# PD_Filter_Amp.net
KiCad netlist of a schematic drawn in EAGLE
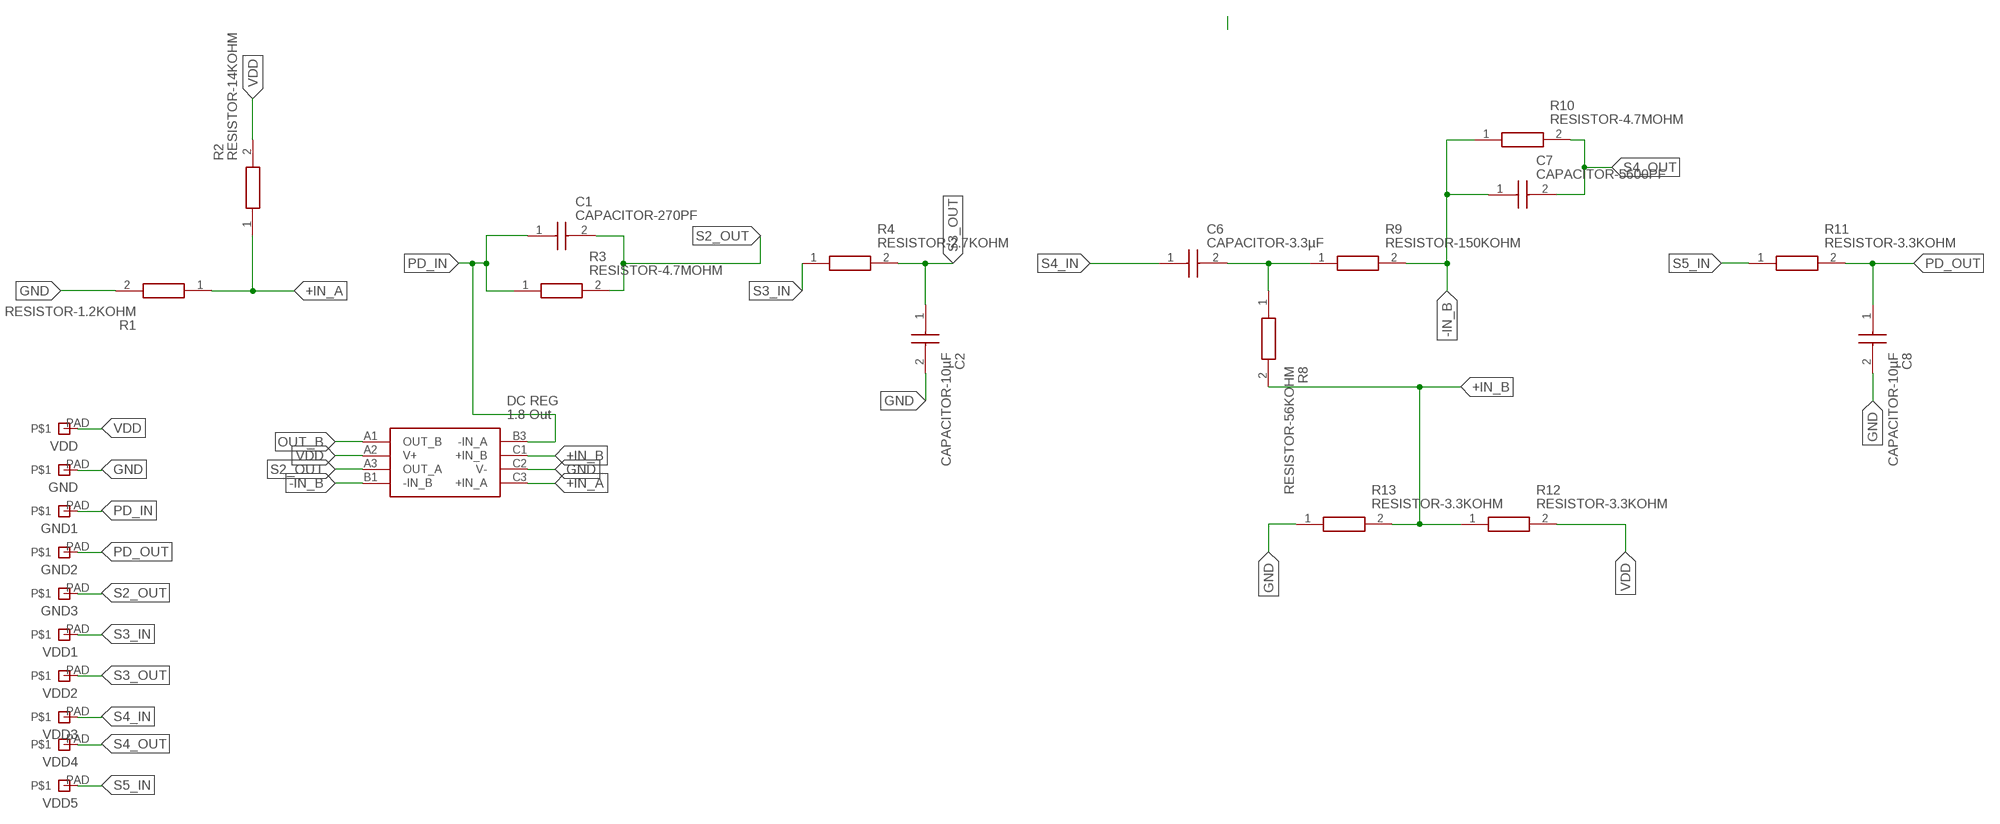
[diagram p0: schematic, sheet 1]

(export (version "E")
  (design (tool "Eeschema 10.0.6"))
  (components
    (comp (ref "C1")
      (value "CAPACITOR-270PF")
      (footprint "eagle-import:CAPC1005X55N")
      (fields
        (field (name "MANUFACTURER_PART_NUMBER") "C0402C271G5GACTU")
        (field (name "MOUSER_PART_NUMBER") "80-C0402C271G5G")
      )
      (libsource (lib "eagle-import") (part "CAPACITOR-270PF"))
    )
    (comp (ref "C2")
      (value "CAPACITOR-10µF")
      (footprint "eagle-import:C0402")
      (fields
        (field (name "MANUFACTURER_PART_NUMBER") "C0402C106M9PACTU")
        (field (name "MOUSER_PART_NUMBER") "80-C0402C106M9P")
      )
      (libsource (lib "eagle-import") (part "CAPACITOR-10µF"))
    )
    (comp (ref "C6")
      (value "CAPACITOR-3.3µF")
      (footprint "eagle-import:C0402")
      (fields
        (field (name "MANUFACTURER_PART_NUMBER") "C0402C335M7PACTU")
        (field (name "MOUSER_PART_NUMBER") "80-C0402C335M7P")
      )
      (libsource (lib "eagle-import") (part "CAPACITOR-3.3µF"))
    )
    (comp (ref "C7")
      (value "CAPACITOR-5600PF")
      (footprint "eagle-import:CAPC1005X55N")
      (fields
        (field (name "MANUFACTURER_PART_NUMBER") "C0402C562J4RACTU")
        (field (name "MOUSER_PART_NUMBER") "80-C0402C562J4R")
      )
      (libsource (lib "eagle-import") (part "CAPACITOR-5600PF"))
    )
    (comp (ref "C8")
      (value "CAPACITOR-10µF")
      (footprint "eagle-import:C0402")
      (fields
        (field (name "MANUFACTURER_PART_NUMBER") "C0402C106M9PACTU")
        (field (name "MOUSER_PART_NUMBER") "80-C0402C106M9P")
      )
      (libsource (lib "eagle-import") (part "CAPACITOR-10µF"))
    )
    (comp (ref "GND")
      (value "PAD")
      (footprint "eagle-import:PAD")
      (libsource (lib "eagle-import") (part "PAD"))
    )
    (comp (ref "GND1")
      (value "PAD")
      (footprint "eagle-import:PAD")
      (libsource (lib "eagle-import") (part "PAD"))
    )
    (comp (ref "GND2")
      (value "PAD")
      (footprint "eagle-import:PAD")
      (libsource (lib "eagle-import") (part "PAD"))
    )
    (comp (ref "GND3")
      (value "PAD")
      (footprint "eagle-import:PAD")
      (libsource (lib "eagle-import") (part "PAD"))
    )
    (comp (ref "IC1")
      (value "ADA4505-2")
      (footprint "eagle-import:BGA8C50P3X3_142X142X65")
      (fields
        (field (name "MANUFACTURER_PART_NUMBER") "ADA4505-2ACBZ-R7")
        (field (name "MOUSER_PART_NUMBER") "584-ADA4505-2ACBZ-R7")
      )
      (libsource (lib "eagle-import") (part "ADA4505-2"))
    )
    (comp (ref "R1")
      (value "RESISTOR-1.2KOHM")
      (footprint "eagle-import:ERJPA2_(0402)")
      (fields
        (field (name "MANUFACTURER_PART_NUMBER") "ERJ-PA2D1201X")
        (field (name "MOUSER_PART_NUMBER") "667-ERJ-PA2D1201X")
      )
      (libsource (lib "eagle-import") (part "RESISTOR-1.2KOHM"))
    )
    (comp (ref "R2")
      (value "RESISTOR-14KOHM")
      (footprint "eagle-import:ERJ2RKD1004X")
      (fields
        (field (name "MANUFACTURER_PART_NUMBER") "ERJ-2RKF1402X")
        (field (name "MOUSER_PART_NUMBER") "667-ERJ-2RKF1402X")
      )
      (libsource (lib "eagle-import") (part "RESISTOR-14KOHM"))
    )
    (comp (ref "R3")
      (value "RESISTOR-4.7MOHM")
      (footprint "eagle-import:ERJ2RKD1004X")
      (fields
        (field (name "MANUFACTURER_PART_NUMBER") "ERJ-2GEJ475X")
        (field (name "MOUSER_PART_NUMBER") "667-ERJ-2GEJ475X")
      )
      (libsource (lib "eagle-import") (part "RESISTOR-4.7MOHM"))
    )
    (comp (ref "R4")
      (value "RESISTOR-2.7KOHM")
      (footprint "eagle-import:ERJPA2_(0402)")
      (fields (field (name "MANUFACTURER_PART_NUMBER") "ERJ-PA2F2701X"))
      (libsource (lib "eagle-import") (part "RESISTOR-2.7KOHM"))
    )
    (comp (ref "R8")
      (value "RESISTOR-56KOHM")
      (footprint "eagle-import:ERJ2RKD1004X")
      (fields
        (field (name "MANUFACTURER_PART_NUMBER") "ERJ-2RKF5602X")
        (field (name "MOUSER_PART_NUMBER") "667-ERJ-2RKF5602X")
      )
      (libsource (lib "eagle-import") (part "RESISTOR-56KOHM"))
    )
    (comp (ref "R9")
      (value "RESISTOR-150KOHM")
      (footprint "eagle-import:ERJS02_U02_(0402)")
      (fields
        (field (name "MANUFACTURER_PART_NUMBER") "ERJ-U02D1503X")
        (field (name "MOUSER_PART_NUMBER") "667-ERJ-U02D1503X")
      )
      (libsource (lib "eagle-import") (part "RESISTOR-150KOHM"))
    )
    (comp (ref "R10")
      (value "RESISTOR-4.7MOHM")
      (footprint "eagle-import:ERJ2RKD1004X")
      (fields
        (field (name "MANUFACTURER_PART_NUMBER") "ERJ-2GEJ475X")
        (field (name "MOUSER_PART_NUMBER") "667-ERJ-2GEJ475X")
      )
      (libsource (lib "eagle-import") (part "RESISTOR-4.7MOHM"))
    )
    (comp (ref "R11")
      (value "RESISTOR-3.3KOHM")
      (footprint "eagle-import:ERJPA2_(0402)")
      (fields
        (field (name "MANUFACTURER_PART_NUMBER") "ERJ-PA2F3301X")
        (field (name "MOUSER_PART_NUMBER") "667-ERJ-PA2F3301X")
      )
      (libsource (lib "eagle-import") (part "RESISTOR-3.3KOHM"))
    )
    (comp (ref "R12")
      (value "RESISTOR-3.3KOHM")
      (footprint "eagle-import:ERJPA2_(0402)")
      (fields
        (field (name "MANUFACTURER_PART_NUMBER") "ERJ-PA2F3301X")
        (field (name "MOUSER_PART_NUMBER") "667-ERJ-PA2F3301X")
      )
      (libsource (lib "eagle-import") (part "RESISTOR-3.3KOHM"))
    )
    (comp (ref "R13")
      (value "RESISTOR-3.3KOHM")
      (footprint "eagle-import:ERJPA2_(0402)")
      (fields
        (field (name "MANUFACTURER_PART_NUMBER") "ERJ-PA2F3301X")
        (field (name "MOUSER_PART_NUMBER") "667-ERJ-PA2F3301X")
      )
      (libsource (lib "eagle-import") (part "RESISTOR-3.3KOHM"))
    )
    (comp (ref "VDD")
      (value "PAD")
      (footprint "eagle-import:PAD")
      (libsource (lib "eagle-import") (part "PAD"))
    )
    (comp (ref "VDD1")
      (value "PAD")
      (footprint "eagle-import:PAD")
      (libsource (lib "eagle-import") (part "PAD"))
    )
    (comp (ref "VDD2")
      (value "PAD")
      (footprint "eagle-import:PAD")
      (libsource (lib "eagle-import") (part "PAD"))
    )
    (comp (ref "VDD3")
      (value "PAD")
      (footprint "eagle-import:PAD")
      (libsource (lib "eagle-import") (part "PAD"))
    )
    (comp (ref "VDD4")
      (value "PAD")
      (footprint "eagle-import:PAD")
      (libsource (lib "eagle-import") (part "PAD"))
    )
    (comp (ref "VDD5")
      (value "PAD")
      (footprint "eagle-import:PAD")
      (libsource (lib "eagle-import") (part "PAD"))
    )
  )
  (nets
    (net (code "1") (name "+IN_A") (class "Default")
      (node (ref "IC1") (pin "C3") (pinfunction "+IN_A_C3") (pintype "bidirectional"))
      (node (ref "R1") (pin "1") (pinfunction "1_1") (pintype "bidirectional"))
      (node (ref "R2") (pin "1") (pinfunction "1_1") (pintype "bidirectional"))
    )
    (net (code "2") (name "+IN_B") (class "Default")
      (node (ref "IC1") (pin "C1") (pinfunction "+IN_B_C1") (pintype "bidirectional"))
      (node (ref "R12") (pin "1") (pinfunction "1_1") (pintype "bidirectional"))
      (node (ref "R13") (pin "2") (pinfunction "2_2") (pintype "bidirectional"))
      (node (ref "R8") (pin "2") (pinfunction "2_2") (pintype "bidirectional"))
    )
    (net (code "3") (name "-IN_B") (class "Default")
      (node (ref "C7") (pin "1") (pinfunction "1_1") (pintype "bidirectional"))
      (node (ref "IC1") (pin "B1") (pinfunction "-IN_B_B1") (pintype "bidirectional"))
      (node (ref "R10") (pin "1") (pinfunction "1_1") (pintype "bidirectional"))
      (node (ref "R9") (pin "2") (pinfunction "2_2") (pintype "bidirectional"))
    )
    (net (code "4") (name "GND") (class "Default")
      (node (ref "C2") (pin "2") (pinfunction "2_2") (pintype "bidirectional"))
      (node (ref "C8") (pin "2") (pinfunction "2_2") (pintype "bidirectional"))
      (node (ref "GND") (pin "PAD") (pinfunction "P$1_PAD") (pintype "bidirectional"))
      (node (ref "IC1") (pin "C2") (pinfunction "V-_C2") (pintype "bidirectional"))
      (node (ref "R1") (pin "2") (pinfunction "2_2") (pintype "bidirectional"))
      (node (ref "R13") (pin "1") (pinfunction "1_1") (pintype "bidirectional"))
    )
    (net (code "5") (name "Net-(C6-Pad2)") (class "Default")
      (node (ref "C6") (pin "2") (pinfunction "2_2") (pintype "bidirectional"))
      (node (ref "R8") (pin "1") (pinfunction "1_1") (pintype "bidirectional"))
      (node (ref "R9") (pin "1") (pinfunction "1_1") (pintype "bidirectional"))
    )
    (net (code "6") (name "OUT_B") (class "Default")
      (node (ref "IC1") (pin "A1") (pinfunction "OUT_B_A1") (pintype "bidirectional"))
    )
    (net (code "7") (name "PD_IN") (class "Default")
      (node (ref "C1") (pin "1") (pinfunction "1_1") (pintype "bidirectional"))
      (node (ref "GND1") (pin "PAD") (pinfunction "P$1_PAD") (pintype "bidirectional"))
      (node (ref "IC1") (pin "B3") (pinfunction "-IN_A_B3") (pintype "bidirectional"))
      (node (ref "R3") (pin "1") (pinfunction "1_1") (pintype "bidirectional"))
    )
    (net (code "8") (name "PD_OUT") (class "Default")
      (node (ref "C8") (pin "1") (pinfunction "1_1") (pintype "bidirectional"))
      (node (ref "GND2") (pin "PAD") (pinfunction "P$1_PAD") (pintype "bidirectional"))
      (node (ref "R11") (pin "2") (pinfunction "2_2") (pintype "bidirectional"))
    )
    (net (code "9") (name "S2_OUT") (class "Default")
      (node (ref "C1") (pin "2") (pinfunction "2_2") (pintype "bidirectional"))
      (node (ref "GND3") (pin "PAD") (pinfunction "P$1_PAD") (pintype "bidirectional"))
      (node (ref "IC1") (pin "A3") (pinfunction "OUT_A_A3") (pintype "bidirectional"))
      (node (ref "R3") (pin "2") (pinfunction "2_2") (pintype "bidirectional"))
    )
    (net (code "10") (name "S3_IN") (class "Default")
      (node (ref "R4") (pin "1") (pinfunction "1_1") (pintype "bidirectional"))
      (node (ref "VDD1") (pin "PAD") (pinfunction "P$1_PAD") (pintype "bidirectional"))
    )
    (net (code "11") (name "S3_OUT") (class "Default")
      (node (ref "C2") (pin "1") (pinfunction "1_1") (pintype "bidirectional"))
      (node (ref "R4") (pin "2") (pinfunction "2_2") (pintype "bidirectional"))
      (node (ref "VDD2") (pin "PAD") (pinfunction "P$1_PAD") (pintype "bidirectional"))
    )
    (net (code "12") (name "S4_IN") (class "Default")
      (node (ref "C6") (pin "1") (pinfunction "1_1") (pintype "bidirectional"))
      (node (ref "VDD3") (pin "PAD") (pinfunction "P$1_PAD") (pintype "bidirectional"))
    )
    (net (code "13") (name "S4_OUT") (class "Default")
      (node (ref "C7") (pin "2") (pinfunction "2_2") (pintype "bidirectional"))
      (node (ref "R10") (pin "2") (pinfunction "2_2") (pintype "bidirectional"))
      (node (ref "VDD4") (pin "PAD") (pinfunction "P$1_PAD") (pintype "bidirectional"))
    )
    (net (code "14") (name "S5_IN") (class "Default")
      (node (ref "R11") (pin "1") (pinfunction "1_1") (pintype "bidirectional"))
      (node (ref "VDD5") (pin "PAD") (pinfunction "P$1_PAD") (pintype "bidirectional"))
    )
    (net (code "15") (name "VDD") (class "Default")
      (node (ref "IC1") (pin "A2") (pinfunction "V+_A2") (pintype "bidirectional"))
      (node (ref "R12") (pin "2") (pinfunction "2_2") (pintype "bidirectional"))
      (node (ref "R2") (pin "2") (pinfunction "2_2") (pintype "bidirectional"))
      (node (ref "VDD") (pin "PAD") (pinfunction "P$1_PAD") (pintype "bidirectional"))
    )
  )
)
